# 4_0__TK040_31pin.net
KiCad netlist of a schematic drawn in Altium Designer
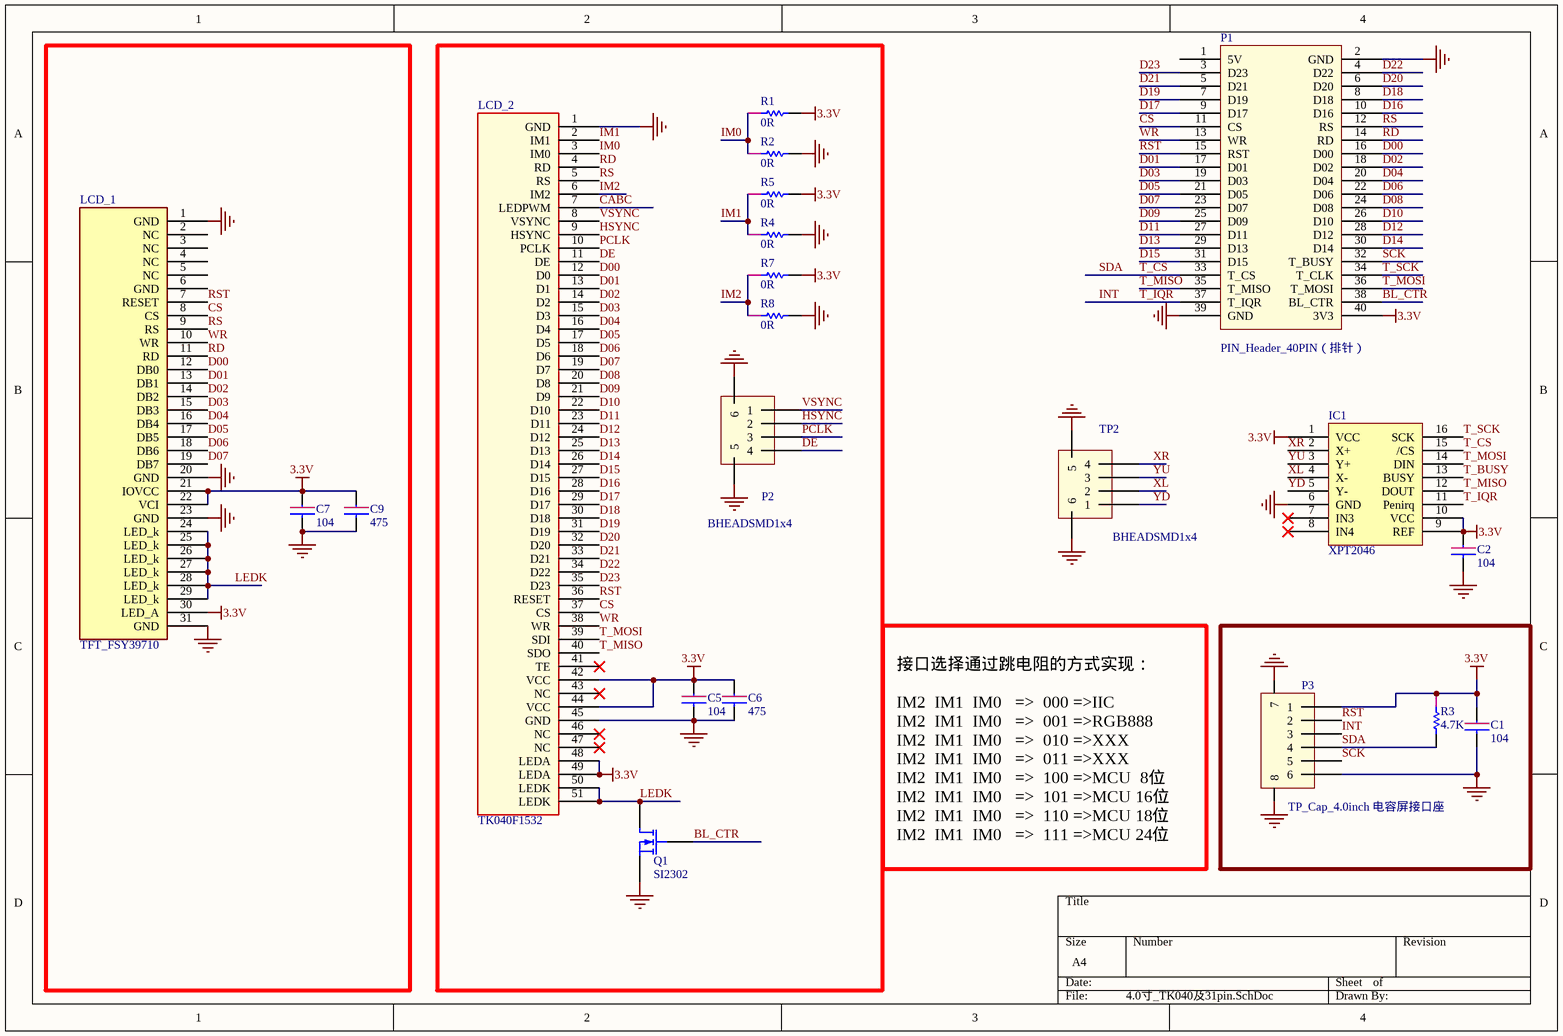
[diagram p0: 4.0寸_TK040及31pin.SchDoc]

(export (version "E")
  (design (tool "Eeschema 10.0.6"))
  (components
    (comp (ref "C1") (value "104") (footprint "C0603-1") (libsource (lib "Tiky") (part "cap")))
    (comp (ref "C2") (value "104") (footprint "C0603-2") (libsource (lib "Tiky") (part "cap")))
    (comp (ref "C5") (value "104") (footprint "C0603-1") (libsource (lib "Tiky") (part "cap")))
    (comp (ref "C6") (value "475") (footprint "C0603-2") (libsource (lib "Tiky") (part "cap")))
    (comp (ref "C7") (value "104") (footprint "C0603-1") (libsource (lib "Tiky") (part "cap")))
    (comp (ref "C9") (value "475") (footprint "C0603-1") (libsource (lib "Tiky") (part "cap")))
    (comp (ref "IC1") (value "XPT2046") (footprint "SOT403-1") (libsource (lib "Tiky") (part "ADS7843")))
    (comp (ref "LCD_1")
      (value "TFT_FSY39710")
      (footprint "TFT_FSY39710")
      (libsource (lib "Tiky") (part "TFT_FSY39710"))
    )
    (comp (ref "LCD_2")
      (value "TK040F1532")
      (footprint "TK040F1532")
      (libsource (lib "Tiky") (part "TK040F1532"))
    )
    (comp (ref "P1")
      (value "PIN_Header_40PIN（排针）")
      (footprint "P_Head_2x20")
      (libsource (lib "Tiky") (part "PIN_Header_40PIN"))
    )
    (comp (ref "P2")
      (value "BHEADSMD1x4")
      (footprint "BHEADSMD1x4")
      (libsource (lib "Tiky") (part "BHEADSMD1x4"))
    )
    (comp (ref "P3")
      (value "TP_Cap_4.0inch 电容屏接口座")
      (footprint "TP_Cap_4.0inch")
      (libsource (lib "Tiky") (part "BHEADSMD1x6"))
    )
    (comp (ref "Q1") (value "SI2302") (footprint "SOT23A") (libsource (lib "Tiky") (part "MOSFET-N")))
    (comp (ref "R1") (value "0R") (footprint "R0603") (libsource (lib "Tiky") (part "Resistor")))
    (comp (ref "R2") (value "0R") (footprint "R0603") (libsource (lib "Tiky") (part "Resistor")))
    (comp (ref "R3") (value "4.7K") (footprint "R0603") (libsource (lib "Tiky") (part "Resistor")))
    (comp (ref "R4") (value "0R") (footprint "R0603") (libsource (lib "Tiky") (part "Resistor")))
    (comp (ref "R5") (value "0R") (footprint "R0603") (libsource (lib "Tiky") (part "Resistor")))
    (comp (ref "R7") (value "0R") (footprint "R0603") (libsource (lib "Tiky") (part "Resistor")))
    (comp (ref "R8") (value "0R") (footprint "R0603") (libsource (lib "Tiky") (part "Resistor")))
    (comp (ref "TP2")
      (value "BHEADSMD1x4")
      (footprint "TP_4.0inch")
      (libsource (lib "") (part "BHEADSMD1x4_1"))
    )
  )
  (nets
    (net (code "1") (name "/BL_CTR") (class "Default")
      (node (ref "P1") (pin "38") (pinfunction "BL_CTR_38") (pintype "passive"))
      (node (ref "Q1") (pin "1") (pinfunction "G_1") (pintype "passive"))
    )
    (net (code "2") (name "/CABC") (class "Default")
      (node (ref "LCD_2") (pin "7") (pinfunction "LEDPWM_7") (pintype "passive"))
    )
    (net (code "3") (name "/CS") (class "Default")
      (node (ref "LCD_1") (pin "8") (pinfunction "CS_8") (pintype "passive"))
      (node (ref "LCD_2") (pin "37") (pinfunction "CS_37") (pintype "passive"))
      (node (ref "P1") (pin "11") (pinfunction "CS_11") (pintype "passive"))
    )
    (net (code "4") (name "/D00") (class "Default")
      (node (ref "LCD_1") (pin "12") (pinfunction "DB0_12") (pintype "passive"))
      (node (ref "LCD_2") (pin "12") (pinfunction "D0_12") (pintype "passive"))
      (node (ref "P1") (pin "16") (pinfunction "D00_16") (pintype "passive"))
    )
    (net (code "5") (name "/D01") (class "Default")
      (node (ref "LCD_1") (pin "13") (pinfunction "DB1_13") (pintype "passive"))
      (node (ref "LCD_2") (pin "13") (pinfunction "D1_13") (pintype "passive"))
      (node (ref "P1") (pin "17") (pinfunction "D01_17") (pintype "passive"))
    )
    (net (code "6") (name "/D02") (class "Default")
      (node (ref "LCD_1") (pin "14") (pinfunction "DB2_14") (pintype "passive"))
      (node (ref "LCD_2") (pin "14") (pinfunction "D2_14") (pintype "passive"))
      (node (ref "P1") (pin "18") (pinfunction "D02_18") (pintype "passive"))
    )
    (net (code "7") (name "/D03") (class "Default")
      (node (ref "LCD_1") (pin "15") (pinfunction "DB3_15") (pintype "passive"))
      (node (ref "LCD_2") (pin "15") (pinfunction "D3_15") (pintype "passive"))
      (node (ref "P1") (pin "19") (pinfunction "D03_19") (pintype "passive"))
    )
    (net (code "8") (name "/D04") (class "Default")
      (node (ref "LCD_1") (pin "16") (pinfunction "DB4_16") (pintype "passive"))
      (node (ref "LCD_2") (pin "16") (pinfunction "D4_16") (pintype "passive"))
      (node (ref "P1") (pin "20") (pinfunction "D04_20") (pintype "passive"))
    )
    (net (code "9") (name "/D05") (class "Default")
      (node (ref "LCD_1") (pin "17") (pinfunction "DB5_17") (pintype "passive"))
      (node (ref "LCD_2") (pin "17") (pinfunction "D5_17") (pintype "passive"))
      (node (ref "P1") (pin "21") (pinfunction "D05_21") (pintype "passive"))
    )
    (net (code "10") (name "/D06") (class "Default")
      (node (ref "LCD_1") (pin "18") (pinfunction "DB6_18") (pintype "passive"))
      (node (ref "LCD_2") (pin "18") (pinfunction "D6_18") (pintype "passive"))
      (node (ref "P1") (pin "22") (pinfunction "D06_22") (pintype "passive"))
    )
    (net (code "11") (name "/D07") (class "Default")
      (node (ref "LCD_1") (pin "19") (pinfunction "DB7_19") (pintype "passive"))
      (node (ref "LCD_2") (pin "19") (pinfunction "D7_19") (pintype "passive"))
      (node (ref "P1") (pin "23") (pinfunction "D07_23") (pintype "passive"))
    )
    (net (code "12") (name "/D08") (class "Default")
      (node (ref "LCD_2") (pin "20") (pinfunction "D8_20") (pintype "passive"))
      (node (ref "P1") (pin "24") (pinfunction "D08_24") (pintype "passive"))
    )
    (net (code "13") (name "/D09") (class "Default")
      (node (ref "LCD_2") (pin "21") (pinfunction "D9_21") (pintype "passive"))
      (node (ref "P1") (pin "25") (pinfunction "D09_25") (pintype "passive"))
    )
    (net (code "14") (name "/D10") (class "Default")
      (node (ref "LCD_2") (pin "22") (pinfunction "D10_22") (pintype "passive"))
      (node (ref "P1") (pin "26") (pinfunction "D10_26") (pintype "passive"))
    )
    (net (code "15") (name "/D11") (class "Default")
      (node (ref "LCD_2") (pin "23") (pinfunction "D11_23") (pintype "passive"))
      (node (ref "P1") (pin "27") (pinfunction "D11_27") (pintype "passive"))
    )
    (net (code "16") (name "/D12") (class "Default")
      (node (ref "LCD_2") (pin "24") (pinfunction "D12_24") (pintype "passive"))
      (node (ref "P1") (pin "28") (pinfunction "D12_28") (pintype "passive"))
    )
    (net (code "17") (name "/D13") (class "Default")
      (node (ref "LCD_2") (pin "25") (pinfunction "D13_25") (pintype "passive"))
      (node (ref "P1") (pin "29") (pinfunction "D13_29") (pintype "passive"))
    )
    (net (code "18") (name "/D14") (class "Default")
      (node (ref "LCD_2") (pin "26") (pinfunction "D14_26") (pintype "passive"))
      (node (ref "P1") (pin "30") (pinfunction "D14_30") (pintype "passive"))
    )
    (net (code "19") (name "/D15") (class "Default")
      (node (ref "LCD_2") (pin "27") (pinfunction "D15_27") (pintype "passive"))
      (node (ref "P1") (pin "31") (pinfunction "D15_31") (pintype "passive"))
    )
    (net (code "20") (name "/D16") (class "Default")
      (node (ref "LCD_2") (pin "28") (pinfunction "D16_28") (pintype "passive"))
      (node (ref "P1") (pin "10") (pinfunction "D16_10") (pintype "passive"))
    )
    (net (code "21") (name "/D17") (class "Default")
      (node (ref "LCD_2") (pin "29") (pinfunction "D17_29") (pintype "passive"))
      (node (ref "P1") (pin "9") (pinfunction "D17_9") (pintype "passive"))
    )
    (net (code "22") (name "/D18") (class "Default")
      (node (ref "LCD_2") (pin "30") (pinfunction "D18_30") (pintype "passive"))
      (node (ref "P1") (pin "8") (pinfunction "D18_8") (pintype "passive"))
    )
    (net (code "23") (name "/D19") (class "Default")
      (node (ref "LCD_2") (pin "31") (pinfunction "D19_31") (pintype "passive"))
      (node (ref "P1") (pin "7") (pinfunction "D19_7") (pintype "passive"))
    )
    (net (code "24") (name "/D20") (class "Default")
      (node (ref "LCD_2") (pin "32") (pinfunction "D20_32") (pintype "passive"))
      (node (ref "P1") (pin "6") (pinfunction "D20_6") (pintype "passive"))
    )
    (net (code "25") (name "/D21") (class "Default")
      (node (ref "LCD_2") (pin "33") (pinfunction "D21_33") (pintype "passive"))
      (node (ref "P1") (pin "5") (pinfunction "D21_5") (pintype "passive"))
    )
    (net (code "26") (name "/D22") (class "Default")
      (node (ref "LCD_2") (pin "34") (pinfunction "D22_34") (pintype "passive"))
      (node (ref "P1") (pin "4") (pinfunction "D22_4") (pintype "passive"))
    )
    (net (code "27") (name "/D23") (class "Default")
      (node (ref "LCD_2") (pin "35") (pinfunction "D23_35") (pintype "passive"))
      (node (ref "P1") (pin "3") (pinfunction "D23_3") (pintype "passive"))
    )
    (net (code "28") (name "/DE") (class "Default")
      (node (ref "LCD_2") (pin "11") (pinfunction "DE_11") (pintype "passive"))
      (node (ref "P2") (pin "4") (pinfunction "4_4") (pintype "passive"))
    )
    (net (code "29") (name "/HSYNC") (class "Default")
      (node (ref "LCD_2") (pin "9") (pinfunction "HSYNC_9") (pintype "passive"))
      (node (ref "P2") (pin "2") (pinfunction "2_2") (pintype "passive"))
    )
    (net (code "30") (name "/IM0") (class "Default")
      (node (ref "LCD_2") (pin "3") (pinfunction "IM0_3") (pintype "passive"))
      (node (ref "R1") (pin "1") (pinfunction "1_1") (pintype "passive"))
      (node (ref "R2") (pin "1") (pinfunction "1_1") (pintype "passive"))
    )
    (net (code "31") (name "/IM1") (class "Default")
      (node (ref "LCD_2") (pin "2") (pinfunction "IM1_2") (pintype "passive"))
      (node (ref "R4") (pin "1") (pinfunction "1_1") (pintype "passive"))
      (node (ref "R5") (pin "1") (pinfunction "1_1") (pintype "passive"))
    )
    (net (code "32") (name "/IM2") (class "Default")
      (node (ref "LCD_2") (pin "6") (pinfunction "IM2_6") (pintype "passive"))
      (node (ref "R7") (pin "1") (pinfunction "1_1") (pintype "passive"))
      (node (ref "R8") (pin "1") (pinfunction "1_1") (pintype "passive"))
    )
    (net (code "33") (name "/INT") (class "Default")
      (node (ref "IC1") (pin "11") (pinfunction "Penirq_11") (pintype "passive"))
      (node (ref "P1") (pin "37") (pinfunction "T_IQR_37") (pintype "passive"))
      (node (ref "P3") (pin "3") (pinfunction "3_3") (pintype "passive"))
    )
    (net (code "34") (name "/LEDK") (class "Default")
      (node (ref "LCD_1") (pin "24") (pinfunction "LED_k_24") (pintype "passive"))
      (node (ref "LCD_1") (pin "25") (pinfunction "LED_k_25") (pintype "passive"))
      (node (ref "LCD_1") (pin "26") (pinfunction "LED_k_26") (pintype "passive"))
      (node (ref "LCD_1") (pin "27") (pinfunction "LED_k_27") (pintype "passive"))
      (node (ref "LCD_1") (pin "28") (pinfunction "LED_k_28") (pintype "passive"))
      (node (ref "LCD_1") (pin "29") (pinfunction "LED_k_29") (pintype "passive"))
      (node (ref "LCD_2") (pin "50") (pinfunction "LEDK_50") (pintype "passive"))
      (node (ref "LCD_2") (pin "51") (pinfunction "LEDK_51") (pintype "passive"))
      (node (ref "Q1") (pin "3") (pinfunction "D_3") (pintype "passive"))
    )
    (net (code "35") (name "/PCLK") (class "Default")
      (node (ref "LCD_2") (pin "10") (pinfunction "PCLK_10") (pintype "passive"))
      (node (ref "P2") (pin "3") (pinfunction "3_3") (pintype "passive"))
    )
    (net (code "36") (name "/RD") (class "Default")
      (node (ref "LCD_1") (pin "11") (pinfunction "RD_11") (pintype "passive"))
      (node (ref "LCD_2") (pin "4") (pinfunction "RD_4") (pintype "passive"))
      (node (ref "P1") (pin "14") (pinfunction "RD_14") (pintype "passive"))
    )
    (net (code "37") (name "/RS") (class "Default")
      (node (ref "LCD_1") (pin "9") (pinfunction "RS_9") (pintype "passive"))
      (node (ref "LCD_2") (pin "5") (pinfunction "RS_5") (pintype "passive"))
      (node (ref "P1") (pin "12") (pinfunction "RS_12") (pintype "passive"))
    )
    (net (code "38") (name "/RST") (class "Default")
      (node (ref "LCD_1") (pin "7") (pinfunction "RESET_7") (pintype "passive"))
      (node (ref "LCD_2") (pin "36") (pinfunction "RESET_36") (pintype "passive"))
      (node (ref "P1") (pin "15") (pinfunction "RST_15") (pintype "passive"))
      (node (ref "P3") (pin "2") (pinfunction "2_2") (pintype "passive"))
    )
    (net (code "39") (name "/SCK") (class "Default")
      (node (ref "P1") (pin "32") (pinfunction "T_BUSY_32") (pintype "passive"))
      (node (ref "P3") (pin "5") (pinfunction "5_5") (pintype "passive"))
    )
    (net (code "40") (name "/SDA") (class "Default")
      (node (ref "IC1") (pin "15") (pinfunction "/CS_15") (pintype "passive"))
      (node (ref "P1") (pin "33") (pinfunction "T_CS_33") (pintype "passive"))
      (node (ref "P3") (pin "4") (pinfunction "4_4") (pintype "passive"))
      (node (ref "R3") (pin "2") (pinfunction "2_2") (pintype "passive"))
    )
    (net (code "41") (name "/T_BUSY") (class "Default")
      (node (ref "IC1") (pin "13") (pinfunction "BUSY_13") (pintype "passive"))
    )
    (net (code "42") (name "/T_MISO") (class "Default")
      (node (ref "IC1") (pin "12") (pinfunction "DOUT_12") (pintype "passive"))
      (node (ref "LCD_2") (pin "40") (pinfunction "SDO_40") (pintype "passive"))
      (node (ref "P1") (pin "35") (pinfunction "T_MISO_35") (pintype "passive"))
    )
    (net (code "43") (name "/T_MOSI") (class "Default")
      (node (ref "IC1") (pin "14") (pinfunction "DIN_14") (pintype "passive"))
      (node (ref "LCD_2") (pin "39") (pinfunction "SDI_39") (pintype "passive"))
      (node (ref "P1") (pin "36") (pinfunction "T_MOSI_36") (pintype "passive"))
    )
    (net (code "44") (name "/T_SCK") (class "Default")
      (node (ref "IC1") (pin "16") (pinfunction "SCK_16") (pintype "passive"))
      (node (ref "P1") (pin "34") (pinfunction "T_CLK_34") (pintype "passive"))
    )
    (net (code "45") (name "/VSYNC") (class "Default")
      (node (ref "LCD_2") (pin "8") (pinfunction "VSYNC_8") (pintype "passive"))
      (node (ref "P2") (pin "1") (pinfunction "1_1") (pintype "passive"))
    )
    (net (code "46") (name "/WR") (class "Default")
      (node (ref "LCD_1") (pin "10") (pinfunction "WR_10") (pintype "passive"))
      (node (ref "LCD_2") (pin "38") (pinfunction "WR_38") (pintype "passive"))
      (node (ref "P1") (pin "13") (pinfunction "WR_13") (pintype "passive"))
    )
    (net (code "47") (name "/XL") (class "Default")
      (node (ref "IC1") (pin "4") (pinfunction "X-_4") (pintype "passive"))
      (node (ref "TP2") (pin "2") (pinfunction "2_2") (pintype "passive"))
    )
    (net (code "48") (name "/XR") (class "Default")
      (node (ref "IC1") (pin "2") (pinfunction "X+_2") (pintype "passive"))
      (node (ref "TP2") (pin "4") (pinfunction "4_4") (pintype "passive"))
    )
    (net (code "49") (name "/YD") (class "Default")
      (node (ref "IC1") (pin "5") (pinfunction "Y-_5") (pintype "passive"))
      (node (ref "TP2") (pin "1") (pinfunction "1_1") (pintype "passive"))
    )
    (net (code "50") (name "/YU") (class "Default")
      (node (ref "IC1") (pin "3") (pinfunction "Y+_3") (pintype "passive"))
      (node (ref "TP2") (pin "3") (pinfunction "3_3") (pintype "passive"))
    )
    (net (code "51") (name "3.3V") (class "Default")
      (node (ref "C1") (pin "1") (pinfunction "1_1") (pintype "passive"))
      (node (ref "C2") (pin "1") (pinfunction "1_1") (pintype "passive"))
      (node (ref "C5") (pin "1") (pinfunction "1_1") (pintype "passive"))
      (node (ref "C6") (pin "1") (pinfunction "1_1") (pintype "passive"))
      (node (ref "C7") (pin "1") (pinfunction "1_1") (pintype "passive"))
      (node (ref "C9") (pin "1") (pinfunction "1_1") (pintype "passive"))
      (node (ref "IC1") (pin "1") (pinfunction "VCC_1") (pintype "passive"))
      (node (ref "IC1") (pin "10") (pinfunction "VCC_10") (pintype "passive"))
      (node (ref "IC1") (pin "9") (pinfunction "REF_9") (pintype "passive"))
      (node (ref "LCD_1") (pin "21") (pinfunction "IOVCC_21") (pintype "passive"))
      (node (ref "LCD_1") (pin "22") (pinfunction "VCI_22") (pintype "passive"))
      (node (ref "LCD_1") (pin "30") (pinfunction "LED_A_30") (pintype "passive"))
      (node (ref "LCD_2") (pin "42") (pinfunction "VCC_42") (pintype "passive"))
      (node (ref "LCD_2") (pin "44") (pinfunction "VCC_44") (pintype "passive"))
      (node (ref "LCD_2") (pin "48") (pinfunction "LEDA_48") (pintype "passive"))
      (node (ref "LCD_2") (pin "49") (pinfunction "LEDA_49") (pintype "passive"))
      (node (ref "P1") (pin "40") (pinfunction "3V3_40") (pintype "passive"))
      (node (ref "P3") (pin "1") (pinfunction "1_1") (pintype "passive"))
      (node (ref "R1") (pin "2") (pinfunction "2_2") (pintype "passive"))
      (node (ref "R3") (pin "1") (pinfunction "1_1") (pintype "passive"))
      (node (ref "R5") (pin "2") (pinfunction "2_2") (pintype "passive"))
      (node (ref "R7") (pin "2") (pinfunction "2_2") (pintype "passive"))
    )
    (net (code "52") (name "GND") (class "Default")
      (node (ref "C1") (pin "2") (pinfunction "2_2") (pintype "passive"))
      (node (ref "C2") (pin "2") (pinfunction "2_2") (pintype "passive"))
      (node (ref "C5") (pin "2") (pinfunction "2_2") (pintype "passive"))
      (node (ref "C6") (pin "2") (pinfunction "2_2") (pintype "passive"))
      (node (ref "C7") (pin "2") (pinfunction "2_2") (pintype "passive"))
      (node (ref "C9") (pin "2") (pinfunction "2_2") (pintype "passive"))
      (node (ref "IC1") (pin "6") (pinfunction "GND_6") (pintype "passive"))
      (node (ref "LCD_1") (pin "1") (pinfunction "GND_1") (pintype "passive"))
      (node (ref "LCD_1") (pin "20") (pinfunction "GND_20") (pintype "passive"))
      (node (ref "LCD_1") (pin "23") (pinfunction "GND_23") (pintype "passive"))
      (node (ref "LCD_1") (pin "31") (pinfunction "GND_31") (pintype "passive"))
      (node (ref "LCD_2") (pin "1") (pinfunction "GND_1") (pintype "passive"))
      (node (ref "LCD_2") (pin "45") (pinfunction "GND_45") (pintype "passive"))
      (node (ref "P1") (pin "2") (pinfunction "GND_2") (pintype "passive"))
      (node (ref "P1") (pin "39") (pinfunction "GND_39") (pintype "passive"))
      (node (ref "P2") (pin "5") (pinfunction "5_5") (pintype "passive"))
      (node (ref "P2") (pin "6") (pinfunction "6_6") (pintype "passive"))
      (node (ref "P3") (pin "6") (pinfunction "6_6") (pintype "passive"))
      (node (ref "P3") (pin "7") (pinfunction "7_7") (pintype "passive"))
      (node (ref "P3") (pin "8") (pinfunction "8_8") (pintype "passive"))
      (node (ref "Q1") (pin "2") (pinfunction "S_2") (pintype "passive"))
      (node (ref "R2") (pin "2") (pinfunction "2_2") (pintype "passive"))
      (node (ref "R4") (pin "2") (pinfunction "2_2") (pintype "passive"))
      (node (ref "R8") (pin "2") (pinfunction "2_2") (pintype "passive"))
      (node (ref "TP2") (pin "5") (pinfunction "5_5") (pintype "passive"))
      (node (ref "TP2") (pin "6") (pinfunction "6_6") (pintype "passive"))
    )
    (net (code "53") (name "unconnected-(IC1-IN3-Pad7)") (class "Default")
      (node (ref "IC1") (pin "7") (pinfunction "IN3_7") (pintype "passive+no_connect"))
    )
    (net (code "54") (name "unconnected-(IC1-IN4-Pad8)") (class "Default")
      (node (ref "IC1") (pin "8") (pinfunction "IN4_8") (pintype "passive+no_connect"))
    )
    (net (code "55") (name "unconnected-(LCD_1-GND-Pad6)") (class "Default")
      (node (ref "LCD_1") (pin "6") (pinfunction "GND_6") (pintype "passive"))
    )
    (net (code "56") (name "unconnected-(LCD_1-NC-Pad2)") (class "Default")
      (node (ref "LCD_1") (pin "2") (pinfunction "NC_2") (pintype "passive"))
    )
    (net (code "57") (name "unconnected-(LCD_1-NC-Pad3)") (class "Default")
      (node (ref "LCD_1") (pin "3") (pinfunction "NC_3") (pintype "passive"))
    )
    (net (code "58") (name "unconnected-(LCD_1-NC-Pad4)") (class "Default")
      (node (ref "LCD_1") (pin "4") (pinfunction "NC_4") (pintype "passive"))
    )
    (net (code "59") (name "unconnected-(LCD_1-NC-Pad5)") (class "Default")
      (node (ref "LCD_1") (pin "5") (pinfunction "NC_5") (pintype "passive"))
    )
    (net (code "60") (name "unconnected-(LCD_2-NC-Pad43)") (class "Default")
      (node (ref "LCD_2") (pin "43") (pinfunction "NC_43") (pintype "passive+no_connect"))
    )
    (net (code "61") (name "unconnected-(LCD_2-NC-Pad46)") (class "Default")
      (node (ref "LCD_2") (pin "46") (pinfunction "NC_46") (pintype "passive+no_connect"))
    )
    (net (code "62") (name "unconnected-(LCD_2-NC-Pad47)") (class "Default")
      (node (ref "LCD_2") (pin "47") (pinfunction "NC_47") (pintype "passive+no_connect"))
    )
    (net (code "63") (name "unconnected-(LCD_2-TE-Pad41)") (class "Default")
      (node (ref "LCD_2") (pin "41") (pinfunction "TE_41") (pintype "passive+no_connect"))
    )
    (net (code "64") (name "unconnected-(P1-5V-Pad1)") (class "Default")
      (node (ref "P1") (pin "1") (pinfunction "5V_1") (pintype "passive"))
    )
  )
)
